# satellites_pcb_th_v1.net
KiCad netlist of a schematic drawn in EAGLE
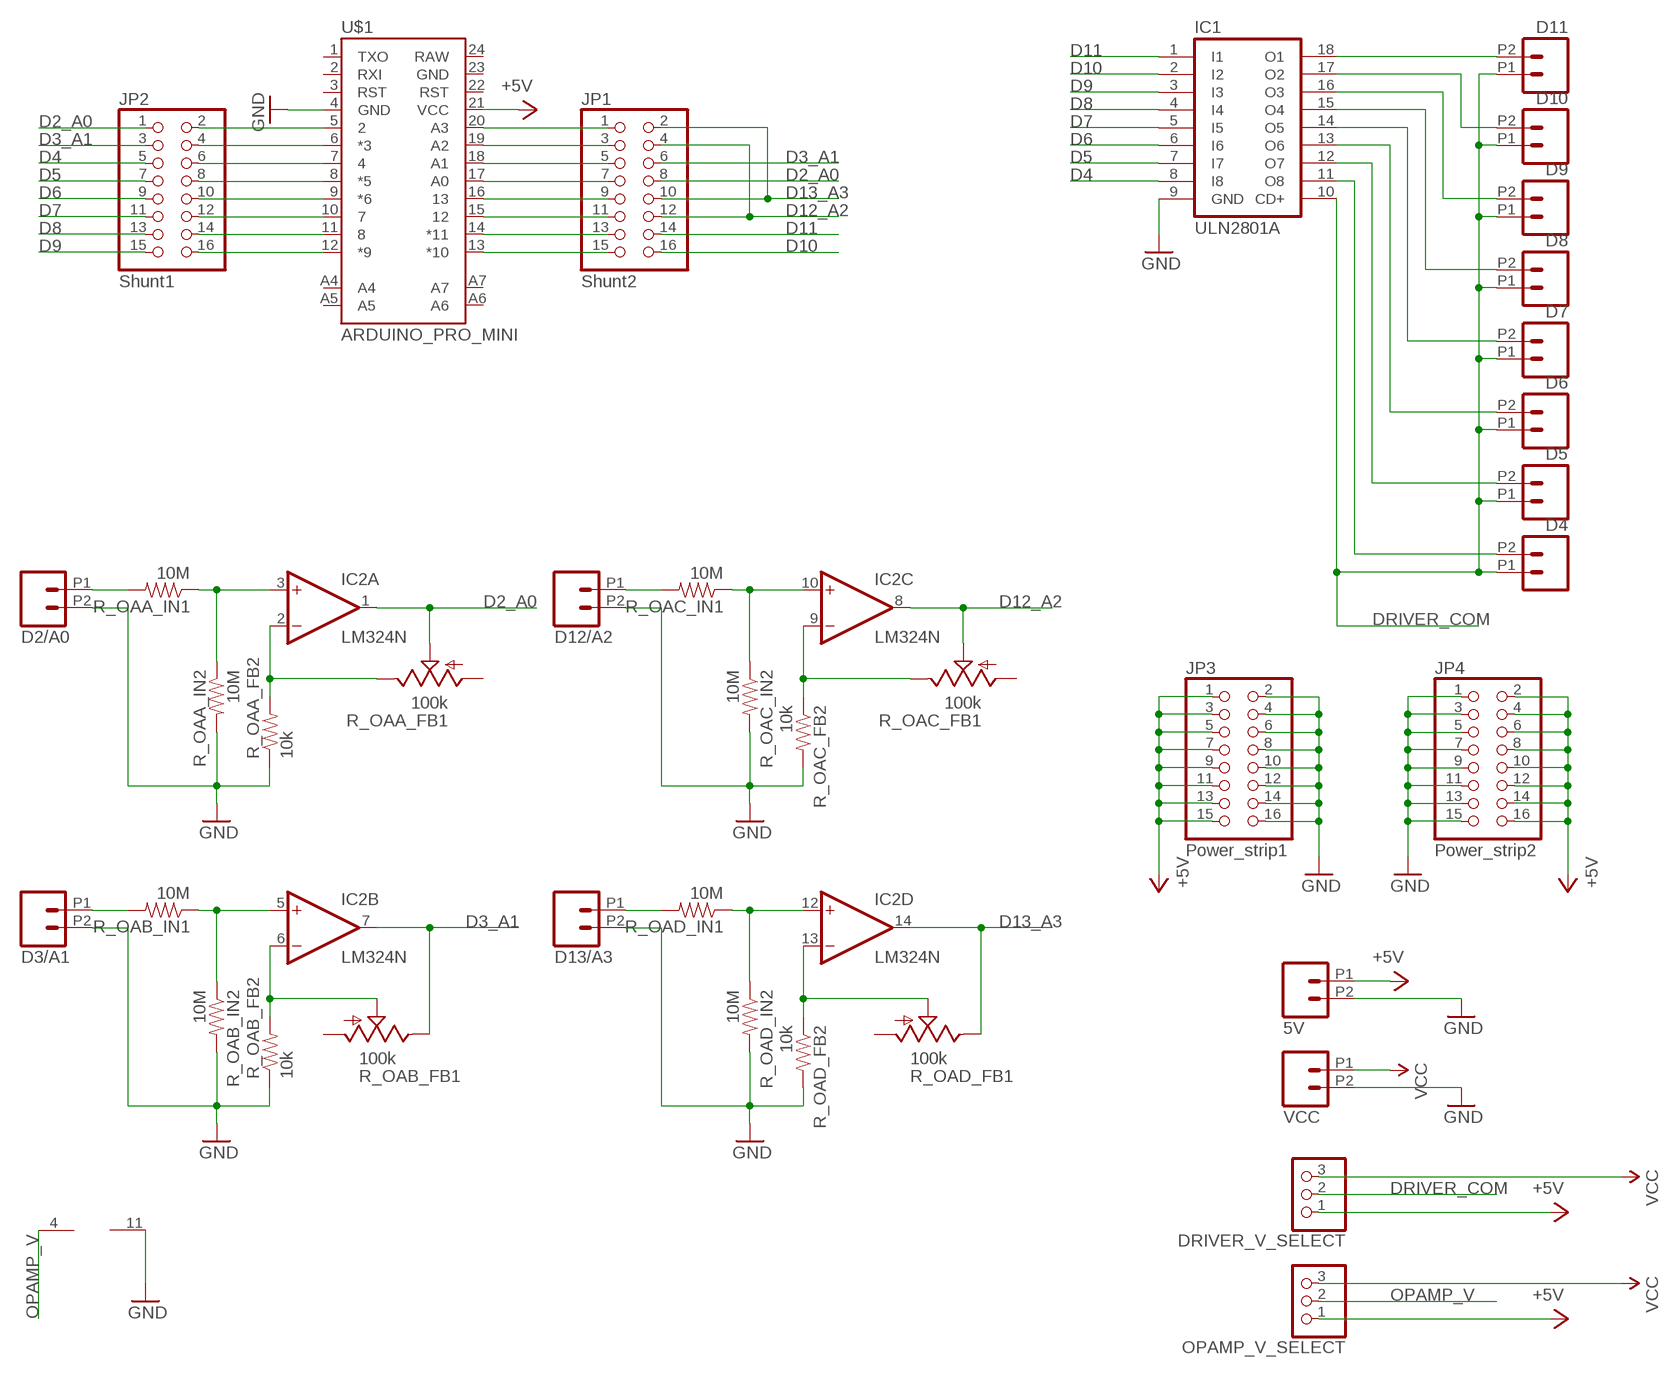
[diagram p0: schematic, sheet 1]

(export (version "E")
  (design (tool "Eeschema 10.0.6"))
  (components
    (comp (ref "5V")
      (value "M022.54MM_SCREWTERM")
      (footprint "eagle-import:1X02_2.54_SCREWTERM")
      (libsource (lib "eagle-import") (part "M022.54MM_SCREWTERM"))
    )
    (comp (ref "D2/A0")
      (value "M022.54MM_SCREWTERM")
      (footprint "eagle-import:1X02_2.54_SCREWTERM")
      (libsource (lib "eagle-import") (part "M022.54MM_SCREWTERM"))
    )
    (comp (ref "D3/A1")
      (value "M022.54MM_SCREWTERM")
      (footprint "eagle-import:1X02_2.54_SCREWTERM")
      (libsource (lib "eagle-import") (part "M022.54MM_SCREWTERM"))
    )
    (comp (ref "D4")
      (value "M022.54MM_SCREWTERM")
      (footprint "eagle-import:1X02_2.54_SCREWTERM")
      (libsource (lib "eagle-import") (part "M022.54MM_SCREWTERM"))
    )
    (comp (ref "D5")
      (value "M022.54MM_SCREWTERM")
      (footprint "eagle-import:1X02_2.54_SCREWTERM")
      (libsource (lib "eagle-import") (part "M022.54MM_SCREWTERM"))
    )
    (comp (ref "D6")
      (value "M022.54MM_SCREWTERM")
      (footprint "eagle-import:1X02_2.54_SCREWTERM")
      (libsource (lib "eagle-import") (part "M022.54MM_SCREWTERM"))
    )
    (comp (ref "D7")
      (value "M022.54MM_SCREWTERM")
      (footprint "eagle-import:1X02_2.54_SCREWTERM")
      (libsource (lib "eagle-import") (part "M022.54MM_SCREWTERM"))
    )
    (comp (ref "D8")
      (value "M022.54MM_SCREWTERM")
      (footprint "eagle-import:1X02_2.54_SCREWTERM")
      (libsource (lib "eagle-import") (part "M022.54MM_SCREWTERM"))
    )
    (comp (ref "D9")
      (value "M022.54MM_SCREWTERM")
      (footprint "eagle-import:1X02_2.54_SCREWTERM")
      (libsource (lib "eagle-import") (part "M022.54MM_SCREWTERM"))
    )
    (comp (ref "D10")
      (value "M022.54MM_SCREWTERM")
      (footprint "eagle-import:1X02_2.54_SCREWTERM")
      (libsource (lib "eagle-import") (part "M022.54MM_SCREWTERM"))
    )
    (comp (ref "D11")
      (value "M022.54MM_SCREWTERM")
      (footprint "eagle-import:1X02_2.54_SCREWTERM")
      (libsource (lib "eagle-import") (part "M022.54MM_SCREWTERM"))
    )
    (comp (ref "D12/A2")
      (value "M022.54MM_SCREWTERM")
      (footprint "eagle-import:1X02_2.54_SCREWTERM")
      (libsource (lib "eagle-import") (part "M022.54MM_SCREWTERM"))
    )
    (comp (ref "D13/A3")
      (value "M022.54MM_SCREWTERM")
      (footprint "eagle-import:1X02_2.54_SCREWTERM")
      (libsource (lib "eagle-import") (part "M022.54MM_SCREWTERM"))
    )
    (comp (ref "DRIVER_V_SELECT")
      (value "PINHD-1X3")
      (footprint "eagle-import:1X03")
      (libsource (lib "eagle-import") (part "PINHD-1X3"))
    )
    (comp (ref "IC1")
      (value "ULN2801A")
      (footprint "eagle-import:DIL18")
      (libsource (lib "eagle-import") (part "ULN2801A"))
    )
    (comp (ref "IC2")
      (value "LM324N")
      (footprint "eagle-import:DIL14")
      (libsource (lib "eagle-import") (part "LM324N"))
    )
    (comp (ref "JP1")
      (value "Shunt2")
      (footprint "eagle-import:2X08")
      (libsource (lib "eagle-import") (part "PINHD-2X8"))
    )
    (comp (ref "JP2")
      (value "Shunt1")
      (footprint "eagle-import:2X08")
      (libsource (lib "eagle-import") (part "PINHD-2X8"))
    )
    (comp (ref "JP3")
      (value "Power_strip1")
      (footprint "eagle-import:2X08")
      (libsource (lib "eagle-import") (part "PINHD-2X8"))
    )
    (comp (ref "JP4")
      (value "Power_strip2")
      (footprint "eagle-import:2X08")
      (libsource (lib "eagle-import") (part "PINHD-2X8"))
    )
    (comp (ref "OPAMP_V_SELECT")
      (value "PINHD-1X3")
      (footprint "eagle-import:1X03")
      (libsource (lib "eagle-import") (part "PINHD-1X3"))
    )
    (comp (ref "R_OAA_FB1")
      (value "100k")
      (footprint "eagle-import:B64W")
      (libsource (lib "eagle-import") (part "TRIM_US-B64W"))
    )
    (comp (ref "R_OAA_FB2")
      (value "10k")
      (footprint "eagle-import:AXIAL-0.3")
      (libsource (lib "eagle-import") (part "RESISTORAXIAL-0.3"))
    )
    (comp (ref "R_OAA_IN1")
      (value "10M")
      (footprint "eagle-import:AXIAL-0.3")
      (libsource (lib "eagle-import") (part "RESISTORAXIAL-0.3"))
    )
    (comp (ref "R_OAA_IN2")
      (value "10M")
      (footprint "eagle-import:AXIAL-0.3")
      (libsource (lib "eagle-import") (part "RESISTORAXIAL-0.3"))
    )
    (comp (ref "R_OAB_FB1")
      (value "100k")
      (footprint "eagle-import:B64W")
      (libsource (lib "eagle-import") (part "TRIM_US-B64W"))
    )
    (comp (ref "R_OAB_FB2")
      (value "10k")
      (footprint "eagle-import:AXIAL-0.3")
      (libsource (lib "eagle-import") (part "RESISTORAXIAL-0.3"))
    )
    (comp (ref "R_OAB_IN1")
      (value "10M")
      (footprint "eagle-import:AXIAL-0.3")
      (libsource (lib "eagle-import") (part "RESISTORAXIAL-0.3"))
    )
    (comp (ref "R_OAB_IN2")
      (value "10M")
      (footprint "eagle-import:AXIAL-0.3")
      (libsource (lib "eagle-import") (part "RESISTORAXIAL-0.3"))
    )
    (comp (ref "R_OAC_FB1")
      (value "100k")
      (footprint "eagle-import:B64W")
      (libsource (lib "eagle-import") (part "TRIM_US-B64W"))
    )
    (comp (ref "R_OAC_FB2")
      (value "10k")
      (footprint "eagle-import:AXIAL-0.3")
      (libsource (lib "eagle-import") (part "RESISTORAXIAL-0.3"))
    )
    (comp (ref "R_OAC_IN1")
      (value "10M")
      (footprint "eagle-import:AXIAL-0.3")
      (libsource (lib "eagle-import") (part "RESISTORAXIAL-0.3"))
    )
    (comp (ref "R_OAC_IN2")
      (value "10M")
      (footprint "eagle-import:AXIAL-0.3")
      (libsource (lib "eagle-import") (part "RESISTORAXIAL-0.3"))
    )
    (comp (ref "R_OAD_FB1")
      (value "100k")
      (footprint "eagle-import:B64W")
      (libsource (lib "eagle-import") (part "TRIM_US-B64W"))
    )
    (comp (ref "R_OAD_FB2")
      (value "10k")
      (footprint "eagle-import:AXIAL-0.3")
      (libsource (lib "eagle-import") (part "RESISTORAXIAL-0.3"))
    )
    (comp (ref "R_OAD_IN1")
      (value "10M")
      (footprint "eagle-import:AXIAL-0.3")
      (libsource (lib "eagle-import") (part "RESISTORAXIAL-0.3"))
    )
    (comp (ref "R_OAD_IN2")
      (value "10M")
      (footprint "eagle-import:AXIAL-0.3")
      (libsource (lib "eagle-import") (part "RESISTORAXIAL-0.3"))
    )
    (comp (ref "U$1")
      (value "ARDUINO_PRO_MINI")
      (footprint "eagle-import:ARDUINO_PRO_MINI")
      (libsource (lib "eagle-import") (part "ARDUINO_PRO_MINI"))
    )
    (comp (ref "VCC")
      (value "M022.54MM_SCREWTERM")
      (footprint "eagle-import:1X02_2.54_SCREWTERM")
      (libsource (lib "eagle-import") (part "M022.54MM_SCREWTERM"))
    )
  )
  (nets
    (net (code "1") (name "+5V") (class "Default")
      (node (ref "5V") (pin "P1") (pinfunction "1_P1") (pintype "passive"))
      (node (ref "DRIVER_V_SELECT") (pin "1") (pinfunction "1_1") (pintype "passive"))
      (node (ref "JP3") (pin "1") (pinfunction "1_1") (pintype "passive"))
      (node (ref "JP3") (pin "11") (pinfunction "11_11") (pintype "passive"))
      (node (ref "JP3") (pin "13") (pinfunction "13_13") (pintype "passive"))
      (node (ref "JP3") (pin "15") (pinfunction "15_15") (pintype "passive"))
      (node (ref "JP3") (pin "3") (pinfunction "3_3") (pintype "passive"))
      (node (ref "JP3") (pin "5") (pinfunction "5_5") (pintype "passive"))
      (node (ref "JP3") (pin "7") (pinfunction "7_7") (pintype "passive"))
      (node (ref "JP3") (pin "9") (pinfunction "9_9") (pintype "passive"))
      (node (ref "JP4") (pin "10") (pinfunction "10_10") (pintype "passive"))
      (node (ref "JP4") (pin "12") (pinfunction "12_12") (pintype "passive"))
      (node (ref "JP4") (pin "14") (pinfunction "14_14") (pintype "passive"))
      (node (ref "JP4") (pin "16") (pinfunction "16_16") (pintype "passive"))
      (node (ref "JP4") (pin "2") (pinfunction "2_2") (pintype "passive"))
      (node (ref "JP4") (pin "4") (pinfunction "4_4") (pintype "passive"))
      (node (ref "JP4") (pin "6") (pinfunction "6_6") (pintype "passive"))
      (node (ref "JP4") (pin "8") (pinfunction "8_8") (pintype "passive"))
      (node (ref "OPAMP_V_SELECT") (pin "1") (pinfunction "1_1") (pintype "passive"))
      (node (ref "U$1") (pin "21") (pinfunction "VCC_21") (pintype "bidirectional"))
    )
    (net (code "2") (name "/D2_A0") (class "Default")
      (node (ref "IC2") (pin "1") (pinfunction "OUT_1") (pintype "output"))
      (node (ref "JP1") (pin "8") (pinfunction "8_8") (pintype "passive"))
      (node (ref "JP2") (pin "1") (pinfunction "1_1") (pintype "passive"))
      (node (ref "R_OAA_FB1") (pin "S") (pinfunction "S_S") (pintype "passive"))
    )
    (net (code "3") (name "/D3_A1") (class "Default")
      (node (ref "IC2") (pin "7") (pinfunction "OUT_7") (pintype "output"))
      (node (ref "JP1") (pin "6") (pinfunction "6_6") (pintype "passive"))
      (node (ref "JP2") (pin "3") (pinfunction "3_3") (pintype "passive"))
      (node (ref "R_OAB_FB1") (pin "E") (pinfunction "E_E") (pintype "passive"))
    )
    (net (code "4") (name "/D4") (class "Default")
      (node (ref "IC1") (pin "8") (pinfunction "I8_8") (pintype "input"))
      (node (ref "JP2") (pin "5") (pinfunction "5_5") (pintype "passive"))
    )
    (net (code "5") (name "/D5") (class "Default")
      (node (ref "IC1") (pin "7") (pinfunction "I7_7") (pintype "input"))
      (node (ref "JP2") (pin "7") (pinfunction "7_7") (pintype "passive"))
    )
    (net (code "6") (name "/D6") (class "Default")
      (node (ref "IC1") (pin "6") (pinfunction "I6_6") (pintype "input"))
      (node (ref "JP2") (pin "9") (pinfunction "9_9") (pintype "passive"))
    )
    (net (code "7") (name "/D7") (class "Default")
      (node (ref "IC1") (pin "5") (pinfunction "I5_5") (pintype "input"))
      (node (ref "JP2") (pin "11") (pinfunction "11_11") (pintype "passive"))
    )
    (net (code "8") (name "/D8") (class "Default")
      (node (ref "IC1") (pin "4") (pinfunction "I4_4") (pintype "input"))
      (node (ref "JP2") (pin "13") (pinfunction "13_13") (pintype "passive"))
    )
    (net (code "9") (name "/D9") (class "Default")
      (node (ref "IC1") (pin "3") (pinfunction "I3_3") (pintype "input"))
      (node (ref "JP2") (pin "15") (pinfunction "15_15") (pintype "passive"))
    )
    (net (code "10") (name "/D10") (class "Default")
      (node (ref "IC1") (pin "2") (pinfunction "I2_2") (pintype "input"))
      (node (ref "JP1") (pin "16") (pinfunction "16_16") (pintype "passive"))
    )
    (net (code "11") (name "/D11") (class "Default")
      (node (ref "IC1") (pin "1") (pinfunction "I1_1") (pintype "input"))
      (node (ref "JP1") (pin "14") (pinfunction "14_14") (pintype "passive"))
    )
    (net (code "12") (name "/D12_A2") (class "Default")
      (node (ref "IC2") (pin "8") (pinfunction "OUT_8") (pintype "output"))
      (node (ref "JP1") (pin "12") (pinfunction "12_12") (pintype "passive"))
      (node (ref "JP1") (pin "4") (pinfunction "4_4") (pintype "passive"))
      (node (ref "R_OAC_FB1") (pin "S") (pinfunction "S_S") (pintype "passive"))
    )
    (net (code "13") (name "/D13_A3") (class "Default")
      (node (ref "IC2") (pin "14") (pinfunction "OUT_14") (pintype "output"))
      (node (ref "JP1") (pin "10") (pinfunction "10_10") (pintype "passive"))
      (node (ref "JP1") (pin "2") (pinfunction "2_2") (pintype "passive"))
      (node (ref "R_OAD_FB1") (pin "E") (pinfunction "E_E") (pintype "passive"))
    )
    (net (code "14") (name "/DRIVER_COM") (class "Default")
      (node (ref "D10") (pin "P1") (pinfunction "1_P1") (pintype "passive"))
      (node (ref "D11") (pin "P1") (pinfunction "1_P1") (pintype "passive"))
      (node (ref "D4") (pin "P1") (pinfunction "1_P1") (pintype "passive"))
      (node (ref "D5") (pin "P1") (pinfunction "1_P1") (pintype "passive"))
      (node (ref "D6") (pin "P1") (pinfunction "1_P1") (pintype "passive"))
      (node (ref "D7") (pin "P1") (pinfunction "1_P1") (pintype "passive"))
      (node (ref "D8") (pin "P1") (pinfunction "1_P1") (pintype "passive"))
      (node (ref "D9") (pin "P1") (pinfunction "1_P1") (pintype "passive"))
      (node (ref "DRIVER_V_SELECT") (pin "2") (pinfunction "2_2") (pintype "passive"))
      (node (ref "IC1") (pin "10") (pinfunction "CD+_10") (pintype "passive"))
    )
    (net (code "15") (name "/OPAMP_V") (class "Default")
      (node (ref "IC2") (pin "4") (pinfunction "V+_4") (pintype "power_in"))
      (node (ref "OPAMP_V_SELECT") (pin "2") (pinfunction "2_2") (pintype "passive"))
    )
    (net (code "16") (name "GND") (class "Default")
      (node (ref "5V") (pin "P2") (pinfunction "2_P2") (pintype "passive"))
      (node (ref "D12/A2") (pin "P2") (pinfunction "2_P2") (pintype "passive"))
      (node (ref "D13/A3") (pin "P2") (pinfunction "2_P2") (pintype "passive"))
      (node (ref "D2/A0") (pin "P2") (pinfunction "2_P2") (pintype "passive"))
      (node (ref "D3/A1") (pin "P2") (pinfunction "2_P2") (pintype "passive"))
      (node (ref "IC1") (pin "9") (pinfunction "GND_9") (pintype "power_in"))
      (node (ref "IC2") (pin "11") (pinfunction "V-_11") (pintype "power_in"))
      (node (ref "JP3") (pin "10") (pinfunction "10_10") (pintype "passive"))
      (node (ref "JP3") (pin "12") (pinfunction "12_12") (pintype "passive"))
      (node (ref "JP3") (pin "14") (pinfunction "14_14") (pintype "passive"))
      (node (ref "JP3") (pin "16") (pinfunction "16_16") (pintype "passive"))
      (node (ref "JP3") (pin "2") (pinfunction "2_2") (pintype "passive"))
      (node (ref "JP3") (pin "4") (pinfunction "4_4") (pintype "passive"))
      (node (ref "JP3") (pin "6") (pinfunction "6_6") (pintype "passive"))
      (node (ref "JP3") (pin "8") (pinfunction "8_8") (pintype "passive"))
      (node (ref "JP4") (pin "1") (pinfunction "1_1") (pintype "passive"))
      (node (ref "JP4") (pin "11") (pinfunction "11_11") (pintype "passive"))
      (node (ref "JP4") (pin "13") (pinfunction "13_13") (pintype "passive"))
      (node (ref "JP4") (pin "15") (pinfunction "15_15") (pintype "passive"))
      (node (ref "JP4") (pin "3") (pinfunction "3_3") (pintype "passive"))
      (node (ref "JP4") (pin "5") (pinfunction "5_5") (pintype "passive"))
      (node (ref "JP4") (pin "7") (pinfunction "7_7") (pintype "passive"))
      (node (ref "JP4") (pin "9") (pinfunction "9_9") (pintype "passive"))
      (node (ref "R_OAA_FB2") (pin "P$1") (pinfunction "1_P$1") (pintype "passive"))
      (node (ref "R_OAA_IN2") (pin "P$2") (pinfunction "2_P$2") (pintype "passive"))
      (node (ref "R_OAB_FB2") (pin "P$1") (pinfunction "1_P$1") (pintype "passive"))
      (node (ref "R_OAB_IN2") (pin "P$2") (pinfunction "2_P$2") (pintype "passive"))
      (node (ref "R_OAC_FB2") (pin "P$2") (pinfunction "2_P$2") (pintype "passive"))
      (node (ref "R_OAC_IN2") (pin "P$2") (pinfunction "2_P$2") (pintype "passive"))
      (node (ref "R_OAD_FB2") (pin "P$2") (pinfunction "2_P$2") (pintype "passive"))
      (node (ref "R_OAD_IN2") (pin "P$2") (pinfunction "2_P$2") (pintype "passive"))
      (node (ref "U$1") (pin "4") (pinfunction "GND_4") (pintype "bidirectional"))
      (node (ref "VCC") (pin "P2") (pinfunction "2_P2") (pintype "passive"))
    )
    (net (code "17") (name "Net-(D2/A0-1)") (class "Default")
      (node (ref "D2/A0") (pin "P1") (pinfunction "1_P1") (pintype "passive"))
      (node (ref "R_OAA_IN1") (pin "P$2") (pinfunction "2_P$2") (pintype "passive"))
    )
    (net (code "18") (name "Net-(D3/A1-1)") (class "Default")
      (node (ref "D3/A1") (pin "P1") (pinfunction "1_P1") (pintype "passive"))
      (node (ref "R_OAB_IN1") (pin "P$2") (pinfunction "2_P$2") (pintype "passive"))
    )
    (net (code "19") (name "Net-(D4-2)") (class "Default")
      (node (ref "D4") (pin "P2") (pinfunction "2_P2") (pintype "passive"))
      (node (ref "IC1") (pin "11") (pinfunction "O8_11") (pintype "open_collector"))
    )
    (net (code "20") (name "Net-(D5-2)") (class "Default")
      (node (ref "D5") (pin "P2") (pinfunction "2_P2") (pintype "passive"))
      (node (ref "IC1") (pin "12") (pinfunction "O7_12") (pintype "open_collector"))
    )
    (net (code "21") (name "Net-(D6-2)") (class "Default")
      (node (ref "D6") (pin "P2") (pinfunction "2_P2") (pintype "passive"))
      (node (ref "IC1") (pin "13") (pinfunction "O6_13") (pintype "open_collector"))
    )
    (net (code "22") (name "Net-(D7-2)") (class "Default")
      (node (ref "D7") (pin "P2") (pinfunction "2_P2") (pintype "passive"))
      (node (ref "IC1") (pin "14") (pinfunction "O5_14") (pintype "open_collector"))
    )
    (net (code "23") (name "Net-(D8-2)") (class "Default")
      (node (ref "D8") (pin "P2") (pinfunction "2_P2") (pintype "passive"))
      (node (ref "IC1") (pin "15") (pinfunction "O4_15") (pintype "open_collector"))
    )
    (net (code "24") (name "Net-(D9-2)") (class "Default")
      (node (ref "D9") (pin "P2") (pinfunction "2_P2") (pintype "passive"))
      (node (ref "IC1") (pin "16") (pinfunction "O3_16") (pintype "open_collector"))
    )
    (net (code "25") (name "Net-(D10-2)") (class "Default")
      (node (ref "D10") (pin "P2") (pinfunction "2_P2") (pintype "passive"))
      (node (ref "IC1") (pin "17") (pinfunction "O2_17") (pintype "open_collector"))
    )
    (net (code "26") (name "Net-(D11-2)") (class "Default")
      (node (ref "D11") (pin "P2") (pinfunction "2_P2") (pintype "passive"))
      (node (ref "IC1") (pin "18") (pinfunction "O1_18") (pintype "open_collector"))
    )
    (net (code "27") (name "Net-(D12/A2-1)") (class "Default")
      (node (ref "D12/A2") (pin "P1") (pinfunction "1_P1") (pintype "passive"))
      (node (ref "R_OAC_IN1") (pin "P$2") (pinfunction "2_P$2") (pintype "passive"))
    )
    (net (code "28") (name "Net-(D13/A3-1)") (class "Default")
      (node (ref "D13/A3") (pin "P1") (pinfunction "1_P1") (pintype "passive"))
      (node (ref "R_OAD_IN1") (pin "P$2") (pinfunction "2_P$2") (pintype "passive"))
    )
    (net (code "29") (name "Net-(IC2A-+IN)") (class "Default")
      (node (ref "IC2") (pin "3") (pinfunction "+IN_3") (pintype "input"))
      (node (ref "R_OAA_IN1") (pin "P$1") (pinfunction "1_P$1") (pintype "passive"))
      (node (ref "R_OAA_IN2") (pin "P$1") (pinfunction "1_P$1") (pintype "passive"))
    )
    (net (code "30") (name "Net-(IC2A--IN)") (class "Default")
      (node (ref "IC2") (pin "2") (pinfunction "-IN_2") (pintype "input"))
      (node (ref "R_OAA_FB1") (pin "E") (pinfunction "E_E") (pintype "passive"))
      (node (ref "R_OAA_FB2") (pin "P$2") (pinfunction "2_P$2") (pintype "passive"))
    )
    (net (code "31") (name "Net-(IC2B-+IN)") (class "Default")
      (node (ref "IC2") (pin "5") (pinfunction "+IN_5") (pintype "input"))
      (node (ref "R_OAB_IN1") (pin "P$1") (pinfunction "1_P$1") (pintype "passive"))
      (node (ref "R_OAB_IN2") (pin "P$1") (pinfunction "1_P$1") (pintype "passive"))
    )
    (net (code "32") (name "Net-(IC2B--IN)") (class "Default")
      (node (ref "IC2") (pin "6") (pinfunction "-IN_6") (pintype "input"))
      (node (ref "R_OAB_FB1") (pin "S") (pinfunction "S_S") (pintype "passive"))
      (node (ref "R_OAB_FB2") (pin "P$2") (pinfunction "2_P$2") (pintype "passive"))
    )
    (net (code "33") (name "Net-(IC2C-+IN)") (class "Default")
      (node (ref "IC2") (pin "10") (pinfunction "+IN_10") (pintype "input"))
      (node (ref "R_OAC_IN1") (pin "P$1") (pinfunction "1_P$1") (pintype "passive"))
      (node (ref "R_OAC_IN2") (pin "P$1") (pinfunction "1_P$1") (pintype "passive"))
    )
    (net (code "34") (name "Net-(IC2C--IN)") (class "Default")
      (node (ref "IC2") (pin "9") (pinfunction "-IN_9") (pintype "input"))
      (node (ref "R_OAC_FB1") (pin "E") (pinfunction "E_E") (pintype "passive"))
      (node (ref "R_OAC_FB2") (pin "P$1") (pinfunction "1_P$1") (pintype "passive"))
    )
    (net (code "35") (name "Net-(IC2D-+IN)") (class "Default")
      (node (ref "IC2") (pin "12") (pinfunction "+IN_12") (pintype "input"))
      (node (ref "R_OAD_IN1") (pin "P$1") (pinfunction "1_P$1") (pintype "passive"))
      (node (ref "R_OAD_IN2") (pin "P$1") (pinfunction "1_P$1") (pintype "passive"))
    )
    (net (code "36") (name "Net-(IC2D--IN)") (class "Default")
      (node (ref "IC2") (pin "13") (pinfunction "-IN_13") (pintype "input"))
      (node (ref "R_OAD_FB1") (pin "S") (pinfunction "S_S") (pintype "passive"))
      (node (ref "R_OAD_FB2") (pin "P$1") (pinfunction "1_P$1") (pintype "passive"))
    )
    (net (code "37") (name "Net-(U$1-*3)") (class "Default")
      (node (ref "JP2") (pin "4") (pinfunction "4_4") (pintype "passive"))
      (node (ref "U$1") (pin "6") (pinfunction "*3_6") (pintype "bidirectional"))
    )
    (net (code "38") (name "Net-(U$1-*5)") (class "Default")
      (node (ref "JP2") (pin "8") (pinfunction "8_8") (pintype "passive"))
      (node (ref "U$1") (pin "8") (pinfunction "*5_8") (pintype "bidirectional"))
    )
    (net (code "39") (name "Net-(U$1-*6)") (class "Default")
      (node (ref "JP2") (pin "10") (pinfunction "10_10") (pintype "passive"))
      (node (ref "U$1") (pin "9") (pinfunction "*6_9") (pintype "bidirectional"))
    )
    (net (code "40") (name "Net-(U$1-*9)") (class "Default")
      (node (ref "JP2") (pin "16") (pinfunction "16_16") (pintype "passive"))
      (node (ref "U$1") (pin "12") (pinfunction "*9_12") (pintype "bidirectional"))
    )
    (net (code "41") (name "Net-(U$1-*10)") (class "Default")
      (node (ref "JP1") (pin "15") (pinfunction "15_15") (pintype "passive"))
      (node (ref "U$1") (pin "13") (pinfunction "*10_13") (pintype "bidirectional"))
    )
    (net (code "42") (name "Net-(U$1-*11)") (class "Default")
      (node (ref "JP1") (pin "13") (pinfunction "13_13") (pintype "passive"))
      (node (ref "U$1") (pin "14") (pinfunction "*11_14") (pintype "bidirectional"))
    )
    (net (code "43") (name "Net-(U$1-2)") (class "Default")
      (node (ref "JP2") (pin "2") (pinfunction "2_2") (pintype "passive"))
      (node (ref "U$1") (pin "5") (pinfunction "2_5") (pintype "bidirectional"))
    )
    (net (code "44") (name "Net-(U$1-4)") (class "Default")
      (node (ref "JP2") (pin "6") (pinfunction "6_6") (pintype "passive"))
      (node (ref "U$1") (pin "7") (pinfunction "4_7") (pintype "bidirectional"))
    )
    (net (code "45") (name "Net-(U$1-7)") (class "Default")
      (node (ref "JP2") (pin "12") (pinfunction "12_12") (pintype "passive"))
      (node (ref "U$1") (pin "10") (pinfunction "7_10") (pintype "bidirectional"))
    )
    (net (code "46") (name "Net-(U$1-8)") (class "Default")
      (node (ref "JP2") (pin "14") (pinfunction "14_14") (pintype "passive"))
      (node (ref "U$1") (pin "11") (pinfunction "8_11") (pintype "bidirectional"))
    )
    (net (code "47") (name "Net-(U$1-12)") (class "Default")
      (node (ref "JP1") (pin "11") (pinfunction "11_11") (pintype "passive"))
      (node (ref "U$1") (pin "15") (pinfunction "12_15") (pintype "bidirectional"))
    )
    (net (code "48") (name "Net-(U$1-13)") (class "Default")
      (node (ref "JP1") (pin "9") (pinfunction "9_9") (pintype "passive"))
      (node (ref "U$1") (pin "16") (pinfunction "13_16") (pintype "bidirectional"))
    )
    (net (code "49") (name "Net-(U$1-A0)") (class "Default")
      (node (ref "JP1") (pin "7") (pinfunction "7_7") (pintype "passive"))
      (node (ref "U$1") (pin "17") (pinfunction "A0_17") (pintype "bidirectional"))
    )
    (net (code "50") (name "Net-(U$1-A1)") (class "Default")
      (node (ref "JP1") (pin "5") (pinfunction "5_5") (pintype "passive"))
      (node (ref "U$1") (pin "18") (pinfunction "A1_18") (pintype "bidirectional"))
    )
    (net (code "51") (name "Net-(U$1-A2)") (class "Default")
      (node (ref "JP1") (pin "3") (pinfunction "3_3") (pintype "passive"))
      (node (ref "U$1") (pin "19") (pinfunction "A2_19") (pintype "bidirectional"))
    )
    (net (code "52") (name "Net-(U$1-A3)") (class "Default")
      (node (ref "JP1") (pin "1") (pinfunction "1_1") (pintype "passive"))
      (node (ref "U$1") (pin "20") (pinfunction "A3_20") (pintype "bidirectional"))
    )
    (net (code "53") (name "VCC") (class "Default")
      (node (ref "DRIVER_V_SELECT") (pin "3") (pinfunction "3_3") (pintype "passive"))
      (node (ref "OPAMP_V_SELECT") (pin "3") (pinfunction "3_3") (pintype "passive"))
      (node (ref "VCC") (pin "P1") (pinfunction "1_P1") (pintype "passive"))
    )
    (net (code "54") (name "unconnected-(R_OAA_FB1-PadA)") (class "Default")
      (node (ref "R_OAA_FB1") (pin "A") (pinfunction "A_A") (pintype "passive"))
    )
    (net (code "55") (name "unconnected-(R_OAB_FB1-PadA)") (class "Default")
      (node (ref "R_OAB_FB1") (pin "A") (pinfunction "A_A") (pintype "passive"))
    )
    (net (code "56") (name "unconnected-(R_OAC_FB1-PadA)") (class "Default")
      (node (ref "R_OAC_FB1") (pin "A") (pinfunction "A_A") (pintype "passive"))
    )
    (net (code "57") (name "unconnected-(R_OAD_FB1-PadA)") (class "Default")
      (node (ref "R_OAD_FB1") (pin "A") (pinfunction "A_A") (pintype "passive"))
    )
    (net (code "58") (name "unconnected-(U$1-GND-Pad23)") (class "Default")
      (node (ref "U$1") (pin "23") (pinfunction "GND_23") (pintype "bidirectional"))
    )
    (net (code "59") (name "unconnected-(U$1-PadA4)") (class "Default")
      (node (ref "U$1") (pin "A4") (pinfunction "A4_A4") (pintype "bidirectional"))
    )
    (net (code "60") (name "unconnected-(U$1-PadA5)") (class "Default")
      (node (ref "U$1") (pin "A5") (pinfunction "A5_A5") (pintype "bidirectional"))
    )
    (net (code "61") (name "unconnected-(U$1-PadA6)") (class "Default")
      (node (ref "U$1") (pin "A6") (pinfunction "A6_A6") (pintype "bidirectional"))
    )
    (net (code "62") (name "unconnected-(U$1-PadA7)") (class "Default")
      (node (ref "U$1") (pin "A7") (pinfunction "A7_A7") (pintype "bidirectional"))
    )
    (net (code "63") (name "unconnected-(U$1-RAW-Pad24)") (class "Default")
      (node (ref "U$1") (pin "24") (pinfunction "RAW_24") (pintype "bidirectional"))
    )
    (net (code "64") (name "unconnected-(U$1-RST-Pad3)") (class "Default")
      (node (ref "U$1") (pin "3") (pinfunction "RST_3") (pintype "bidirectional"))
    )
    (net (code "65") (name "unconnected-(U$1-RST-Pad22)") (class "Default")
      (node (ref "U$1") (pin "22") (pinfunction "RST_22") (pintype "bidirectional"))
    )
    (net (code "66") (name "unconnected-(U$1-RXI-Pad2)") (class "Default")
      (node (ref "U$1") (pin "2") (pinfunction "RXI_2") (pintype "bidirectional"))
    )
    (net (code "67") (name "unconnected-(U$1-TXO-Pad1)") (class "Default")
      (node (ref "U$1") (pin "1") (pinfunction "TXO_1") (pintype "bidirectional"))
    )
  )
)
